# Sheet.net
KiCad netlist of a schematic drawn in Altium Designer
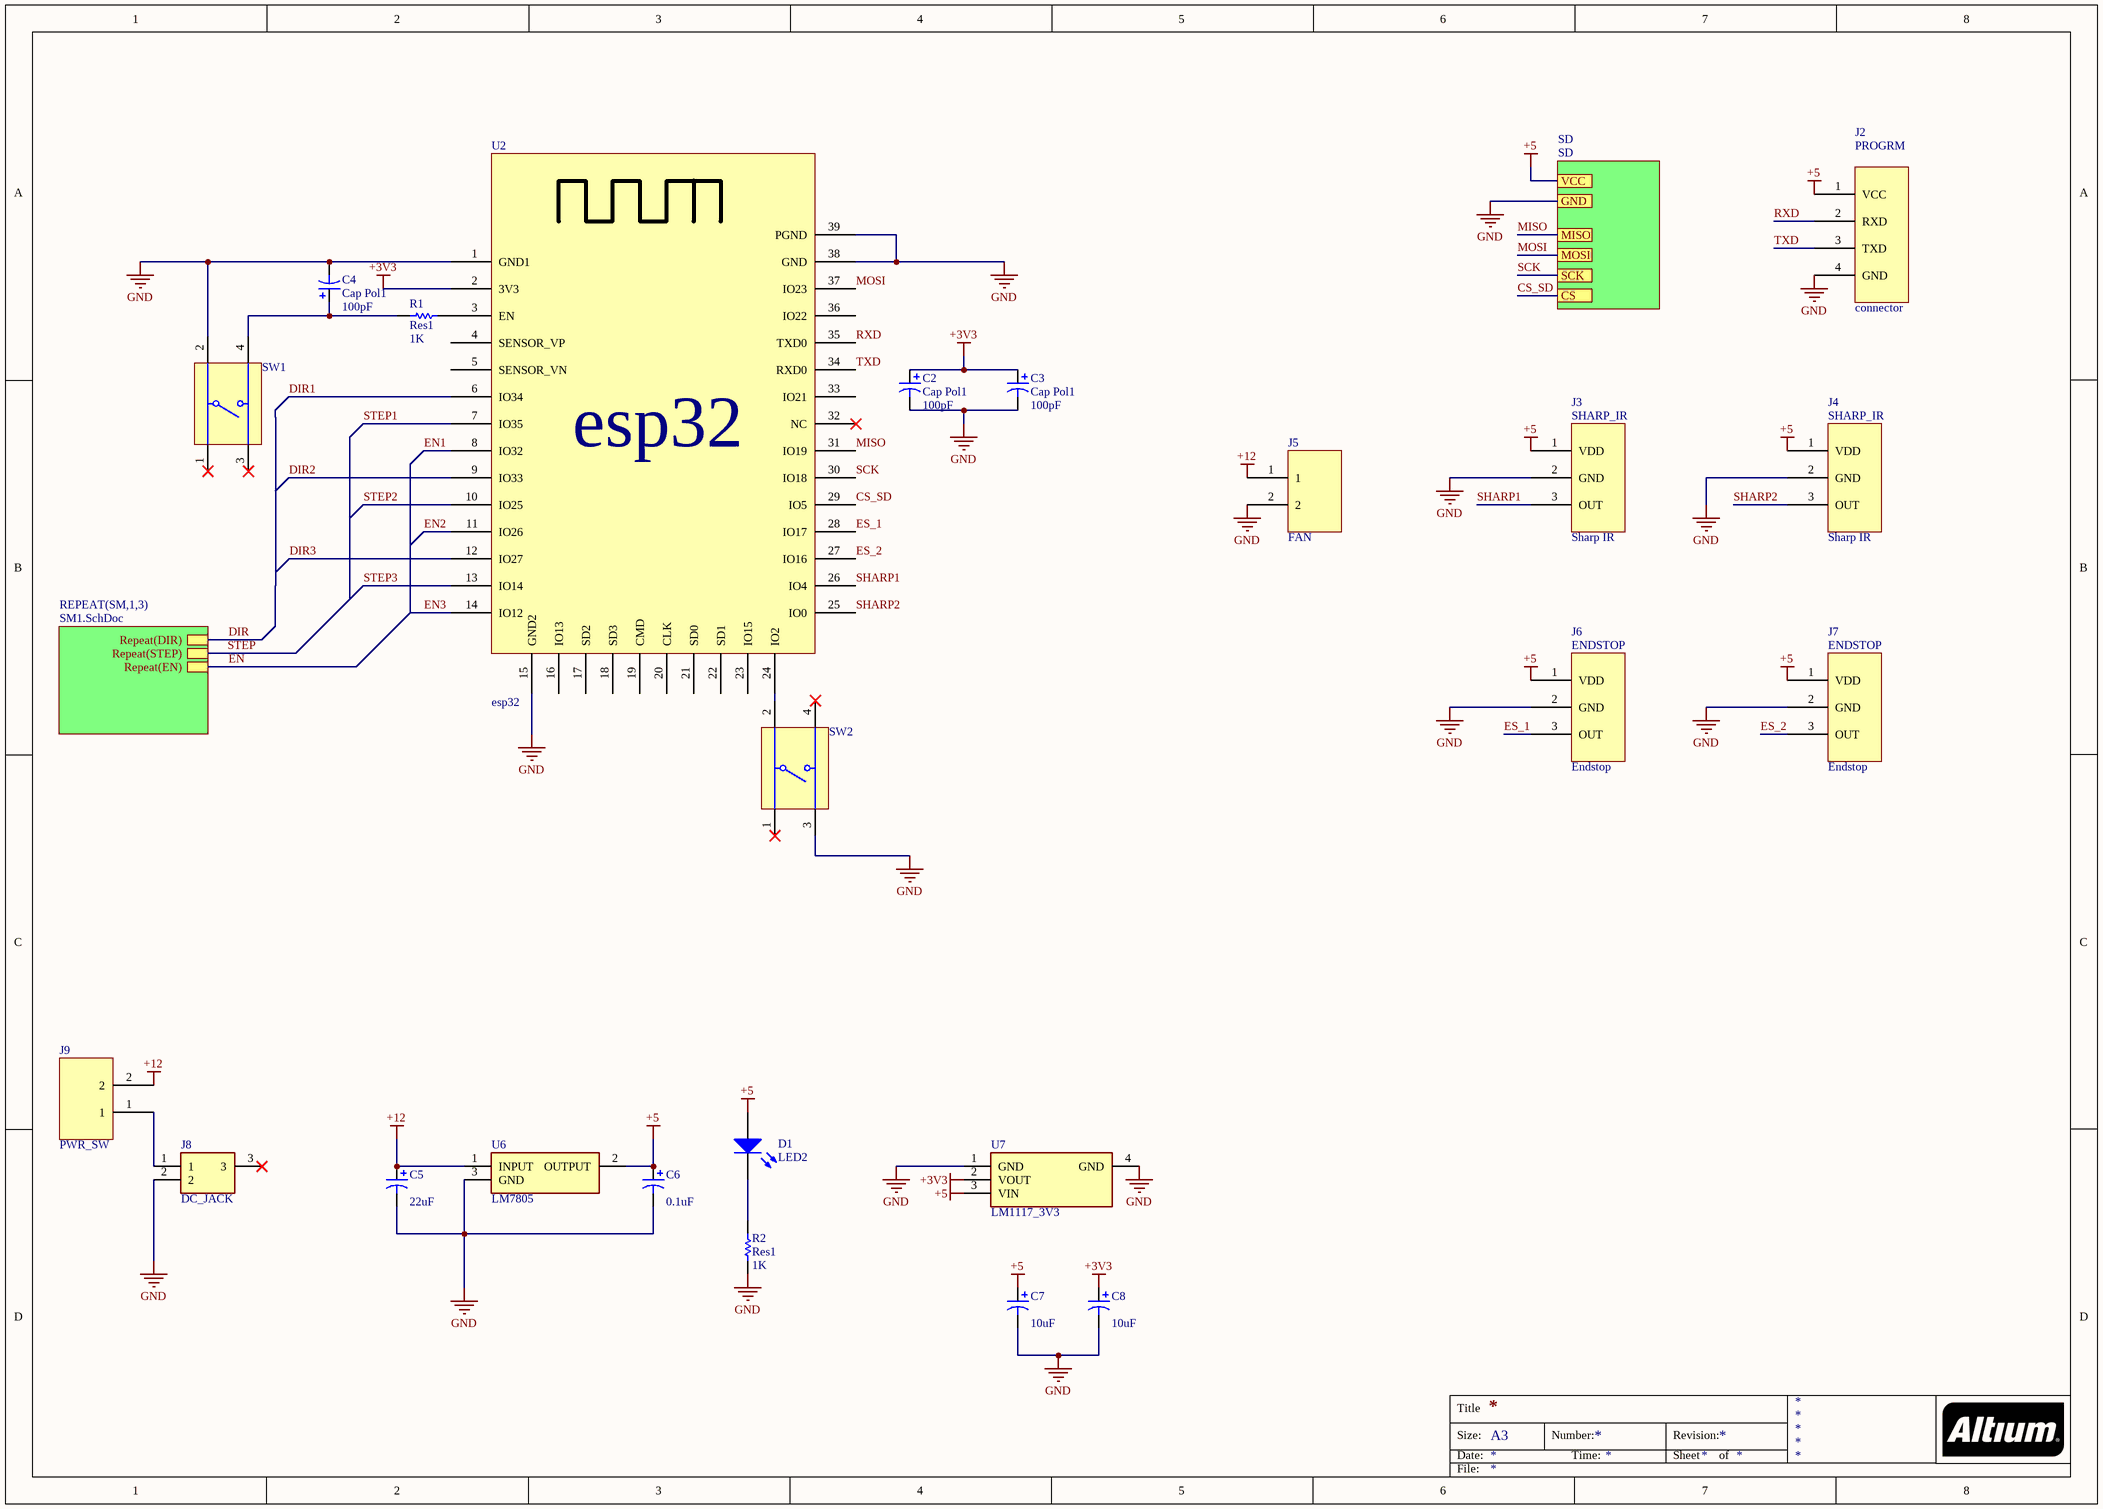
[diagram p0: Sheet.SchDoc]

(export (version "E")
  (design (tool "Eeschema 10.0.6"))
  (components
    (comp (ref "C2")
      (value "Cap Pol1")
      (footprint "6-0805_N")
      (description "Polarized Capacitor (Radial)")
      (fields (field (name "ALTIUM_VALUE") "100pF") (field (name "PUBLISHER") "Altium Limited"))
      (libsource (lib "Miscellaneous Devices") (part "Cap Pol1"))
    )
    (comp (ref "C3")
      (value "Cap Pol1")
      (footprint "6-0805_N")
      (description "Polarized Capacitor (Radial)")
      (fields (field (name "ALTIUM_VALUE") "100pF") (field (name "PUBLISHER") "Altium Limited"))
      (libsource (lib "Miscellaneous Devices") (part "Cap Pol1"))
    )
    (comp (ref "C4")
      (value "Cap Pol1")
      (footprint "6-0805_N")
      (description "Polarized Capacitor (Radial)")
      (fields (field (name "ALTIUM_VALUE") "100pF") (field (name "PUBLISHER") "Altium Limited"))
      (libsource (lib "Miscellaneous Devices") (part "Cap Pol1"))
    )
    (comp (ref "C5")
      (value "22uF")
      (footprint "6-0805_N")
      (description "Polarized Capacitor (Radial)")
      (fields (field (name "Comment") "Cap Pol1") (field (name "PUBLISHER") "Altium Limited"))
      (libsource (lib "Miscellaneous Devices") (part "Cap Pol1"))
    )
    (comp (ref "C6")
      (value "0.1uF")
      (footprint "6-0805_N")
      (description "Polarized Capacitor (Radial)")
      (fields (field (name "Comment") "Cap Pol1") (field (name "PUBLISHER") "Altium Limited"))
      (libsource (lib "Miscellaneous Devices") (part "Cap Pol1"))
    )
    (comp (ref "C7")
      (value "10uF")
      (footprint "6-0805_N")
      (description "Polarized Capacitor (Radial)")
      (fields (field (name "Comment") "Cap Pol1") (field (name "PUBLISHER") "Altium Limited"))
      (libsource (lib "Miscellaneous Devices") (part "Cap Pol1"))
    )
    (comp (ref "C8")
      (value "10uF")
      (footprint "6-0805_N")
      (description "Polarized Capacitor (Radial)")
      (fields (field (name "Comment") "Cap Pol1") (field (name "PUBLISHER") "Altium Limited"))
      (libsource (lib "Miscellaneous Devices") (part "Cap Pol1"))
    )
    (comp (ref "D1")
      (value "LED2")
      (footprint "3.2X1.6X1.1")
      (description "Typical RED, GREEN, YELLOW, AMBER GaAs LED")
      (fields (field (name "PUBLISHER") "Altium Limited"))
      (libsource (lib "Miscellaneous Devices") (part "LED2"))
    )
    (comp (ref "J2") (value "connector") (footprint "TTL") (libsource (lib "Schlib") (part "TTL")))
    (comp (ref "J3") (value "Sharp IR") (footprint "SHARP_IR") (libsource (lib "Schlib") (part "SHARP_IR")))
    (comp (ref "J4") (value "Sharp IR") (footprint "SHARP_IR") (libsource (lib "Schlib") (part "SHARP_IR")))
    (comp (ref "J5") (value "FAN") (footprint "JST_2P") (libsource (lib "Schlib") (part "JST_2P")))
    (comp (ref "J6") (value "Endstop") (footprint "ENDSTOP") (libsource (lib "Schlib") (part "ENDSTOP")))
    (comp (ref "J7") (value "Endstop") (footprint "ENDSTOP") (libsource (lib "Schlib") (part "ENDSTOP")))
    (comp (ref "J8") (value "DC_JACK") (footprint "DC_JACK") (libsource (lib "Schlib") (part "DC_JACK")))
    (comp (ref "J9") (value "PWR_SW") (footprint "JST_2P") (libsource (lib "3D_Scanner") (part "JST_2P")))
    (comp (ref "R1")
      (value "Res1")
      (footprint "6-0805_N")
      (description "Resistor")
      (fields (field (name "ALTIUM_VALUE") "1K") (field (name "PUBLISHER") "Altium Limited"))
      (libsource (lib "Miscellaneous Devices") (part "Res1"))
    )
    (comp (ref "R2")
      (value "Res1")
      (footprint "6-0805_N")
      (description "Resistor")
      (fields (field (name "ALTIUM_VALUE") "1K") (field (name "PUBLISHER") "Altium Limited"))
      (libsource (lib "Miscellaneous Devices") (part "Res1"))
    )
    (comp (ref "SW1")
      (value "1825910-6")
      (footprint "TECO-1825910-6_V")
      (description "Tact Switch, SPST-NO, 0.05 A, -35 to 85 degC, 4-Pin THD, RoHS, Bulk")
      (fields (field (name "MANUFACTURER") "TE Connectivity"))
      (libsource (lib "Altium Content Vault") (part "SW-SPST-4_A"))
    )
    (comp (ref "SW2")
      (value "1825910-6")
      (footprint "TECO-1825910-6_V")
      (description "Tact Switch, SPST-NO, 0.05 A, -35 to 85 degC, 4-Pin THD, RoHS, Bulk")
      (fields (field (name "MANUFACTURER") "TE Connectivity"))
      (libsource (lib "Altium Content Vault") (part "SW-SPST-4_A"))
    )
    (comp (ref "U2")
      (value "esp32")
      (footprint "ESP_SoC_Module")
      (libsource (lib "Schlib") (part "ESP_SoC_Module"))
    )
    (comp (ref "U6") (value "LM7805") (footprint "LM7805") (libsource (lib "Schlib") (part "LM7805")))
    (comp (ref "U7")
      (value "LM1117_3V3")
      (footprint "LM1117_3V3")
      (libsource (lib "Schlib") (part "LM1117_3V3"))
    )
  )
  (nets
    (net (code "1") (name "+3V3") (class "Default")
      (node (ref "C2") (pin "1") (pinfunction "1_1") (pintype "passive"))
      (node (ref "C3") (pin "1") (pinfunction "1_1") (pintype "passive"))
      (node (ref "C8") (pin "1") (pinfunction "1_1") (pintype "passive"))
      (node (ref "U2") (pin "2") (pinfunction "3V3_2") (pintype "passive"))
      (node (ref "U7") (pin "2") (pinfunction "VOUT_2") (pintype "passive"))
    )
    (net (code "2") (name "+5") (class "Default")
      (node (ref "C6") (pin "1") (pinfunction "1_1") (pintype "passive"))
      (node (ref "C7") (pin "1") (pinfunction "1_1") (pintype "passive"))
      (node (ref "D1") (pin "1") (pinfunction "A_1") (pintype "passive"))
      (node (ref "J2") (pin "1") (pinfunction "VCC_1") (pintype "passive"))
      (node (ref "J3") (pin "1") (pinfunction "VDD_1") (pintype "passive"))
      (node (ref "J4") (pin "1") (pinfunction "VDD_1") (pintype "passive"))
      (node (ref "J6") (pin "1") (pinfunction "VDD_1") (pintype "passive"))
      (node (ref "J7") (pin "1") (pinfunction "VDD_1") (pintype "passive"))
      (node (ref "U6") (pin "2") (pinfunction "OUTPUT_2") (pintype "passive"))
      (node (ref "U7") (pin "3") (pinfunction "VIN_3") (pintype "passive"))
    )
    (net (code "3") (name "+12") (class "Default")
      (node (ref "C5") (pin "1") (pinfunction "1_1") (pintype "passive"))
      (node (ref "J5") (pin "1") (pinfunction "1_1") (pintype "passive"))
      (node (ref "J9") (pin "2") (pinfunction "2_2") (pintype "passive"))
      (node (ref "U6") (pin "1") (pinfunction "INPUT_1") (pintype "passive"))
    )
    (net (code "4") (name "/CS_SD") (class "Default")
      (node (ref "U2") (pin "29") (pinfunction "IO5_29") (pintype "passive"))
    )
    (net (code "6") (name "/DIR1") (class "Default")
      (node (ref "U2") (pin "6") (pinfunction "IO34_6") (pintype "passive"))
    )
    (net (code "7") (name "/DIR2") (class "Default")
      (node (ref "U2") (pin "9") (pinfunction "IO33_9") (pintype "passive"))
    )
    (net (code "8") (name "/DIR3") (class "Default")
      (node (ref "U2") (pin "12") (pinfunction "IO27_12") (pintype "passive"))
    )
    (net (code "10") (name "/EN1") (class "Default")
      (node (ref "U2") (pin "8") (pinfunction "IO32_8") (pintype "passive"))
    )
    (net (code "11") (name "/EN2") (class "Default")
      (node (ref "U2") (pin "11") (pinfunction "IO26_11") (pintype "passive"))
    )
    (net (code "12") (name "/EN3") (class "Default")
      (node (ref "U2") (pin "14") (pinfunction "IO12_14") (pintype "passive"))
    )
    (net (code "13") (name "/ES_1") (class "Default")
      (node (ref "J6") (pin "3") (pinfunction "OUT_3") (pintype "passive"))
      (node (ref "U2") (pin "28") (pinfunction "IO17_28") (pintype "passive"))
    )
    (net (code "14") (name "/ES_2") (class "Default")
      (node (ref "J7") (pin "3") (pinfunction "OUT_3") (pintype "passive"))
      (node (ref "U2") (pin "27") (pinfunction "IO16_27") (pintype "passive"))
    )
    (net (code "15") (name "/MISO") (class "Default")
      (node (ref "U2") (pin "31") (pinfunction "IO19_31") (pintype "passive"))
    )
    (net (code "16") (name "/MOSI") (class "Default")
      (node (ref "U2") (pin "37") (pinfunction "IO23_37") (pintype "passive"))
    )
    (net (code "17") (name "/RXD") (class "Default")
      (node (ref "J2") (pin "2") (pinfunction "RXD_2") (pintype "passive"))
      (node (ref "U2") (pin "35") (pinfunction "TXD0_35") (pintype "passive"))
    )
    (net (code "18") (name "/SCK") (class "Default")
      (node (ref "U2") (pin "30") (pinfunction "IO18_30") (pintype "passive"))
    )
    (net (code "19") (name "/SHARP1") (class "Default")
      (node (ref "J3") (pin "3") (pinfunction "OUT_3") (pintype "passive"))
      (node (ref "U2") (pin "26") (pinfunction "IO4_26") (pintype "passive"))
    )
    (net (code "20") (name "/SHARP2") (class "Default")
      (node (ref "J4") (pin "3") (pinfunction "OUT_3") (pintype "passive"))
      (node (ref "U2") (pin "25") (pinfunction "IO0_25") (pintype "passive"))
    )
    (net (code "22") (name "/STEP1") (class "Default")
      (node (ref "U2") (pin "7") (pinfunction "IO35_7") (pintype "passive"))
    )
    (net (code "23") (name "/STEP2") (class "Default")
      (node (ref "U2") (pin "10") (pinfunction "IO25_10") (pintype "passive"))
    )
    (net (code "24") (name "/STEP3") (class "Default")
      (node (ref "U2") (pin "13") (pinfunction "IO14_13") (pintype "passive"))
    )
    (net (code "25") (name "/TXD") (class "Default")
      (node (ref "J2") (pin "3") (pinfunction "TXD_3") (pintype "passive"))
      (node (ref "U2") (pin "34") (pinfunction "RXD0_34") (pintype "passive"))
    )
    (net (code "26") (name "GND") (class "Default")
      (node (ref "C2") (pin "2") (pinfunction "2_2") (pintype "passive"))
      (node (ref "C3") (pin "2") (pinfunction "2_2") (pintype "passive"))
      (node (ref "C4") (pin "2") (pinfunction "2_2") (pintype "passive"))
      (node (ref "C5") (pin "2") (pinfunction "2_2") (pintype "passive"))
      (node (ref "C6") (pin "2") (pinfunction "2_2") (pintype "passive"))
      (node (ref "C7") (pin "2") (pinfunction "2_2") (pintype "passive"))
      (node (ref "C8") (pin "2") (pinfunction "2_2") (pintype "passive"))
      (node (ref "J2") (pin "4") (pinfunction "GND_4") (pintype "passive"))
      (node (ref "J3") (pin "2") (pinfunction "GND_2") (pintype "passive"))
      (node (ref "J4") (pin "2") (pinfunction "GND_2") (pintype "passive"))
      (node (ref "J5") (pin "2") (pinfunction "2_2") (pintype "passive"))
      (node (ref "J6") (pin "2") (pinfunction "GND_2") (pintype "passive"))
      (node (ref "J7") (pin "2") (pinfunction "GND_2") (pintype "passive"))
      (node (ref "J8") (pin "2") (pinfunction "2_2") (pintype "passive"))
      (node (ref "R2") (pin "1") (pinfunction "1_1") (pintype "passive"))
      (node (ref "SW1") (pin "2") (pinfunction "2_2") (pintype "passive"))
      (node (ref "SW2") (pin "3") (pinfunction "3_3") (pintype "passive"))
      (node (ref "U2") (pin "1") (pinfunction "GND1_1") (pintype "passive"))
      (node (ref "U2") (pin "15") (pinfunction "GND2_15") (pintype "passive"))
      (node (ref "U2") (pin "38") (pinfunction "GND_38") (pintype "passive"))
      (node (ref "U2") (pin "39") (pinfunction "PGND_39") (pintype "passive"))
      (node (ref "U6") (pin "3") (pinfunction "GND_3") (pintype "passive"))
      (node (ref "U7") (pin "1") (pinfunction "GND_1") (pintype "passive"))
      (node (ref "U7") (pin "4") (pinfunction "GND_4") (pintype "passive"))
    )
    (net (code "27") (name "Net-(C4-Pad1)") (class "Default")
      (node (ref "C4") (pin "1") (pinfunction "1_1") (pintype "passive"))
      (node (ref "R1") (pin "1") (pinfunction "1_1") (pintype "passive"))
      (node (ref "SW1") (pin "4") (pinfunction "4_4") (pintype "passive"))
    )
    (net (code "28") (name "Net-(D1-K)") (class "Default")
      (node (ref "D1") (pin "2") (pinfunction "K_2") (pintype "passive"))
      (node (ref "R2") (pin "2") (pinfunction "2_2") (pintype "passive"))
    )
    (net (code "29") (name "Net-(J8-Pad1)") (class "Default")
      (node (ref "J8") (pin "1") (pinfunction "1_1") (pintype "passive"))
      (node (ref "J9") (pin "1") (pinfunction "1_1") (pintype "passive"))
    )
    (net (code "30") (name "Net-(U2-EN)") (class "Default")
      (node (ref "R1") (pin "2") (pinfunction "2_2") (pintype "passive"))
      (node (ref "U2") (pin "3") (pinfunction "EN_3") (pintype "passive"))
    )
    (net (code "31") (name "Net-(U2-IO2)") (class "Default")
      (node (ref "SW2") (pin "2") (pinfunction "2_2") (pintype "passive"))
      (node (ref "U2") (pin "24") (pinfunction "IO2_24") (pintype "passive"))
    )
    (net (code "32") (name "unconnected-(J8-Pad3)") (class "Default")
      (node (ref "J8") (pin "3") (pinfunction "3_3") (pintype "passive+no_connect"))
    )
    (net (code "33") (name "unconnected-(SW1-Pad1)") (class "Default")
      (node (ref "SW1") (pin "1") (pinfunction "1_1") (pintype "passive+no_connect"))
    )
    (net (code "34") (name "unconnected-(SW1-Pad3)") (class "Default")
      (node (ref "SW1") (pin "3") (pinfunction "3_3") (pintype "passive+no_connect"))
    )
    (net (code "35") (name "unconnected-(SW2-Pad1)") (class "Default")
      (node (ref "SW2") (pin "1") (pinfunction "1_1") (pintype "passive+no_connect"))
    )
    (net (code "36") (name "unconnected-(SW2-Pad4)") (class "Default")
      (node (ref "SW2") (pin "4") (pinfunction "4_4") (pintype "passive+no_connect"))
    )
    (net (code "37") (name "unconnected-(U2-CLK-Pad20)") (class "Default")
      (node (ref "U2") (pin "20") (pinfunction "CLK_20") (pintype "passive"))
    )
    (net (code "38") (name "unconnected-(U2-CMD-Pad19)") (class "Default")
      (node (ref "U2") (pin "19") (pinfunction "CMD_19") (pintype "passive"))
    )
    (net (code "39") (name "unconnected-(U2-IO13-Pad16)") (class "Default")
      (node (ref "U2") (pin "16") (pinfunction "IO13_16") (pintype "passive"))
    )
    (net (code "40") (name "unconnected-(U2-IO15-Pad23)") (class "Default")
      (node (ref "U2") (pin "23") (pinfunction "IO15_23") (pintype "passive"))
    )
    (net (code "41") (name "unconnected-(U2-IO21-Pad33)") (class "Default")
      (node (ref "U2") (pin "33") (pinfunction "IO21_33") (pintype "passive"))
    )
    (net (code "42") (name "unconnected-(U2-IO22-Pad36)") (class "Default")
      (node (ref "U2") (pin "36") (pinfunction "IO22_36") (pintype "passive"))
    )
    (net (code "43") (name "unconnected-(U2-NC-Pad32)") (class "Default")
      (node (ref "U2") (pin "32") (pinfunction "NC_32") (pintype "passive+no_connect"))
    )
    (net (code "44") (name "unconnected-(U2-SD0-Pad21)") (class "Default")
      (node (ref "U2") (pin "21") (pinfunction "SD0_21") (pintype "passive"))
    )
    (net (code "45") (name "unconnected-(U2-SD1-Pad22)") (class "Default")
      (node (ref "U2") (pin "22") (pinfunction "SD1_22") (pintype "passive"))
    )
    (net (code "46") (name "unconnected-(U2-SD2-Pad17)") (class "Default")
      (node (ref "U2") (pin "17") (pinfunction "SD2_17") (pintype "passive"))
    )
    (net (code "47") (name "unconnected-(U2-SD3-Pad18)") (class "Default")
      (node (ref "U2") (pin "18") (pinfunction "SD3_18") (pintype "passive"))
    )
    (net (code "48") (name "unconnected-(U2-SENSOR_VN-Pad5)") (class "Default")
      (node (ref "U2") (pin "5") (pinfunction "SENSOR_VN_5") (pintype "passive"))
    )
    (net (code "49") (name "unconnected-(U2-SENSOR_VP-Pad4)") (class "Default")
      (node (ref "U2") (pin "4") (pinfunction "SENSOR_VP_4") (pintype "passive"))
    )
  )
)
